# DW1000.net
KiCad netlist of a schematic drawn in Altium Designer
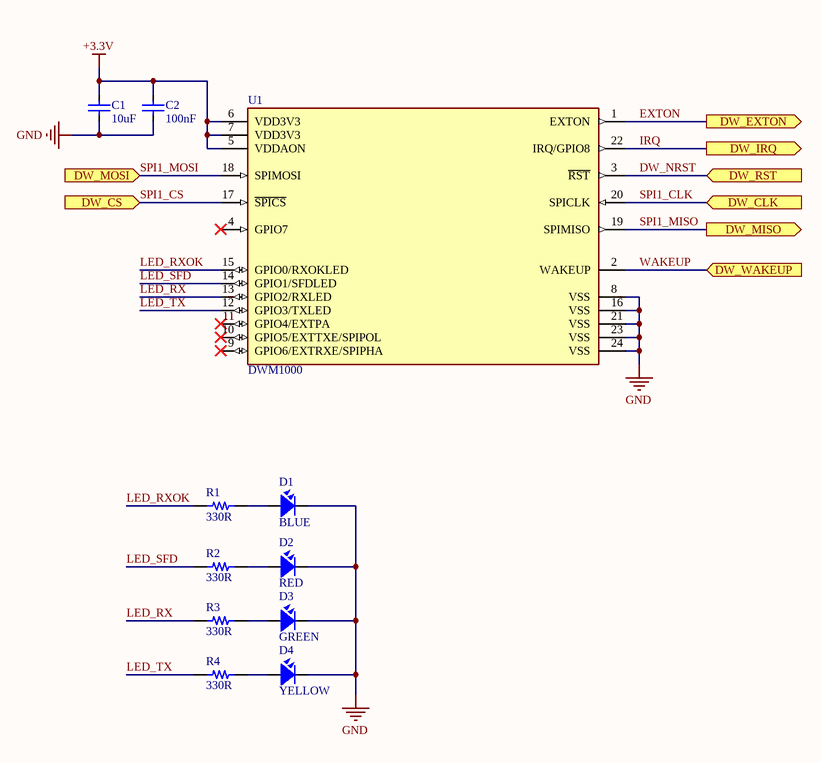
[diagram p0: DW1000.SchDoc]

(export (version "E")
  (design (tool "Eeschema 10.0.6"))
  (components
    (comp (ref "C1")
      (value "10uF")
      (footprint "CAP_0603")
      (description "Capacitor")
      (fields (field (name "PUBLISHER") "Altium Limited"))
      (libsource (lib "My Library") (part "CapSMD"))
    )
    (comp (ref "C2")
      (value "100nF")
      (footprint "CAP_0603")
      (description "Capacitor")
      (fields (field (name "PUBLISHER") "Altium Limited"))
      (libsource (lib "My Library") (part "CapSMD"))
    )
    (comp (ref "D1")
      (value "BLUE")
      (footprint "LED-0603-Green")
      (description "LED Single colour Green and Red")
      (libsource (lib "My Library") (part "LED"))
    )
    (comp (ref "D2")
      (value "RED")
      (footprint "LED-0603-Red")
      (description "LED Single colour Green and Red")
      (libsource (lib "My Library") (part "LED"))
    )
    (comp (ref "D3")
      (value "GREEN")
      (footprint "LED-0603-Green")
      (description "LED Single colour Green and Red")
      (libsource (lib "My Library") (part "LED"))
    )
    (comp (ref "D4")
      (value "YELLOW")
      (footprint "LED-0603-Green")
      (description "LED Single colour Green and Red")
      (libsource (lib "My Library") (part "LED"))
    )
    (comp (ref "R1")
      (value "330R")
      (footprint "RES-SMD-0603")
      (description "Resistor")
      (fields
        (field (name "MANUFACTURER") "Generic Components")
        (field (name "PUBLISHER") "Altium Hobart Technology Centre")
      )
      (libsource (lib "My Library") (part "Resistor - SMD"))
    )
    (comp (ref "R2")
      (value "330R")
      (footprint "RES-SMD-0603")
      (description "Resistor")
      (fields
        (field (name "MANUFACTURER") "Generic Components")
        (field (name "PUBLISHER") "Altium Hobart Technology Centre")
      )
      (libsource (lib "My Library") (part "Resistor - SMD"))
    )
    (comp (ref "R3")
      (value "330R")
      (footprint "RES-SMD-0603")
      (description "Resistor")
      (fields
        (field (name "MANUFACTURER") "Generic Components")
        (field (name "PUBLISHER") "Altium Hobart Technology Centre")
      )
      (libsource (lib "My Library") (part "Resistor - SMD"))
    )
    (comp (ref "R4")
      (value "330R")
      (footprint "RES-SMD-0603")
      (description "Resistor")
      (fields
        (field (name "MANUFACTURER") "Generic Components")
        (field (name "PUBLISHER") "Altium Hobart Technology Centre")
      )
      (libsource (lib "My Library") (part "Resistor - SMD"))
    )
    (comp (ref "U1")
      (value "DWM1000")
      (footprint "DW1000")
      (description "Decawave's DW1000 Ultra\r\nWideband (UWB) transceiver IC")
      (libsource (lib "My Library") (part "DWM1000"))
    )
  )
  (nets
    (net (code "1") (name "+3.3V") (class "Default")
      (node (ref "C1") (pin "2") (pinfunction "2_2") (pintype "passive"))
      (node (ref "C2") (pin "2") (pinfunction "2_2") (pintype "passive"))
      (node (ref "U1") (pin "5") (pinfunction "VDDAON_5") (pintype "power_in"))
      (node (ref "U1") (pin "6") (pinfunction "VDD3V3_6") (pintype "power_in"))
      (node (ref "U1") (pin "7") (pinfunction "VDD3V3_7") (pintype "power_in"))
    )
    (net (code "2") (name "/DW_NRST") (class "Default")
      (node (ref "U1") (pin "3") (pinfunction "~{RST}_3") (pintype "output"))
    )
    (net (code "3") (name "/EXTON") (class "Default")
      (node (ref "U1") (pin "1") (pinfunction "EXTON_1") (pintype "output"))
    )
    (net (code "4") (name "/IRQ") (class "Default")
      (node (ref "U1") (pin "22") (pinfunction "IRQ/GPIO8_22") (pintype "output"))
    )
    (net (code "5") (name "/LED_RX") (class "Default")
      (node (ref "R3") (pin "2") (pinfunction "2_2") (pintype "passive"))
      (node (ref "U1") (pin "13") (pinfunction "GPIO2/RXLED_13") (pintype "bidirectional"))
    )
    (net (code "6") (name "/LED_RXOK") (class "Default")
      (node (ref "R1") (pin "2") (pinfunction "2_2") (pintype "passive"))
      (node (ref "U1") (pin "15") (pinfunction "GPIO0/RXOKLED_15") (pintype "bidirectional"))
    )
    (net (code "7") (name "/LED_SFD") (class "Default")
      (node (ref "R2") (pin "2") (pinfunction "2_2") (pintype "passive"))
      (node (ref "U1") (pin "14") (pinfunction "GPIO1/SFDLED_14") (pintype "bidirectional"))
    )
    (net (code "8") (name "/LED_TX") (class "Default")
      (node (ref "R4") (pin "2") (pinfunction "2_2") (pintype "passive"))
      (node (ref "U1") (pin "12") (pinfunction "GPIO3/TXLED_12") (pintype "bidirectional"))
    )
    (net (code "9") (name "/SPI1_CLK") (class "Default")
      (node (ref "U1") (pin "20") (pinfunction "SPICLK_20") (pintype "input"))
    )
    (net (code "10") (name "/SPI1_CS") (class "Default")
      (node (ref "U1") (pin "17") (pinfunction "~{SPICS}_17") (pintype "input"))
    )
    (net (code "11") (name "/SPI1_MISO") (class "Default")
      (node (ref "U1") (pin "19") (pinfunction "SPIMISO_19") (pintype "output"))
    )
    (net (code "12") (name "/SPI1_MOSI") (class "Default")
      (node (ref "U1") (pin "18") (pinfunction "SPIMOSI_18") (pintype "input"))
    )
    (net (code "13") (name "/WAKEUP") (class "Default")
      (node (ref "U1") (pin "2") (pinfunction "WAKEUP_2") (pintype "passive"))
    )
    (net (code "14") (name "GND") (class "Default")
      (node (ref "C1") (pin "1") (pinfunction "1_1") (pintype "passive"))
      (node (ref "C2") (pin "1") (pinfunction "1_1") (pintype "passive"))
      (node (ref "D1") (pin "2") (pinfunction "2_2") (pintype "passive"))
      (node (ref "D2") (pin "2") (pinfunction "2_2") (pintype "passive"))
      (node (ref "D3") (pin "2") (pinfunction "2_2") (pintype "passive"))
      (node (ref "D4") (pin "2") (pinfunction "2_2") (pintype "passive"))
      (node (ref "U1") (pin "16") (pinfunction "VSS_16") (pintype "power_in"))
      (node (ref "U1") (pin "21") (pinfunction "VSS_21") (pintype "power_in"))
      (node (ref "U1") (pin "23") (pinfunction "VSS_23") (pintype "power_in"))
      (node (ref "U1") (pin "24") (pinfunction "VSS_24") (pintype "power_in"))
      (node (ref "U1") (pin "8") (pinfunction "VSS_8") (pintype "power_in"))
    )
    (net (code "15") (name "Net-(D1-Pad1)") (class "Default")
      (node (ref "D1") (pin "1") (pinfunction "1_1") (pintype "passive"))
      (node (ref "R1") (pin "1") (pinfunction "1_1") (pintype "passive"))
    )
    (net (code "16") (name "Net-(D2-Pad1)") (class "Default")
      (node (ref "D2") (pin "1") (pinfunction "1_1") (pintype "passive"))
      (node (ref "R2") (pin "1") (pinfunction "1_1") (pintype "passive"))
    )
    (net (code "17") (name "Net-(D3-Pad1)") (class "Default")
      (node (ref "D3") (pin "1") (pinfunction "1_1") (pintype "passive"))
      (node (ref "R3") (pin "1") (pinfunction "1_1") (pintype "passive"))
    )
    (net (code "18") (name "Net-(D4-Pad1)") (class "Default")
      (node (ref "D4") (pin "1") (pinfunction "1_1") (pintype "passive"))
      (node (ref "R4") (pin "1") (pinfunction "1_1") (pintype "passive"))
    )
    (net (code "19") (name "unconnected-(U1-GPIO4{slash}EXTPA-Pad11)") (class "Default")
      (node (ref "U1") (pin "11") (pinfunction "GPIO4/EXTPA_11") (pintype "bidirectional+no_connect"))
    )
    (net (code "20") (name "unconnected-(U1-GPIO5{slash}EXTTXE{slash}SPIPOL-Pad10)") (class "Default")
      (node (ref "U1") (pin "10") (pinfunction "GPIO5/EXTTXE/SPIPOL_10") (pintype "bidirectional+no_connect"))
    )
    (net (code "21") (name "unconnected-(U1-GPIO6{slash}EXTRXE{slash}SPIPHA-Pad9)") (class "Default")
      (node (ref "U1") (pin "9") (pinfunction "GPIO6/EXTRXE/SPIPHA_9") (pintype "bidirectional+no_connect"))
    )
    (net (code "22") (name "unconnected-(U1-GPIO7-Pad4)") (class "Default")
      (node (ref "U1") (pin "4") (pinfunction "GPIO7_4") (pintype "input+no_connect"))
    )
  )
)
